# 00-Chopper-AB.net
KiCad netlist of a schematic drawn in Altium Designer
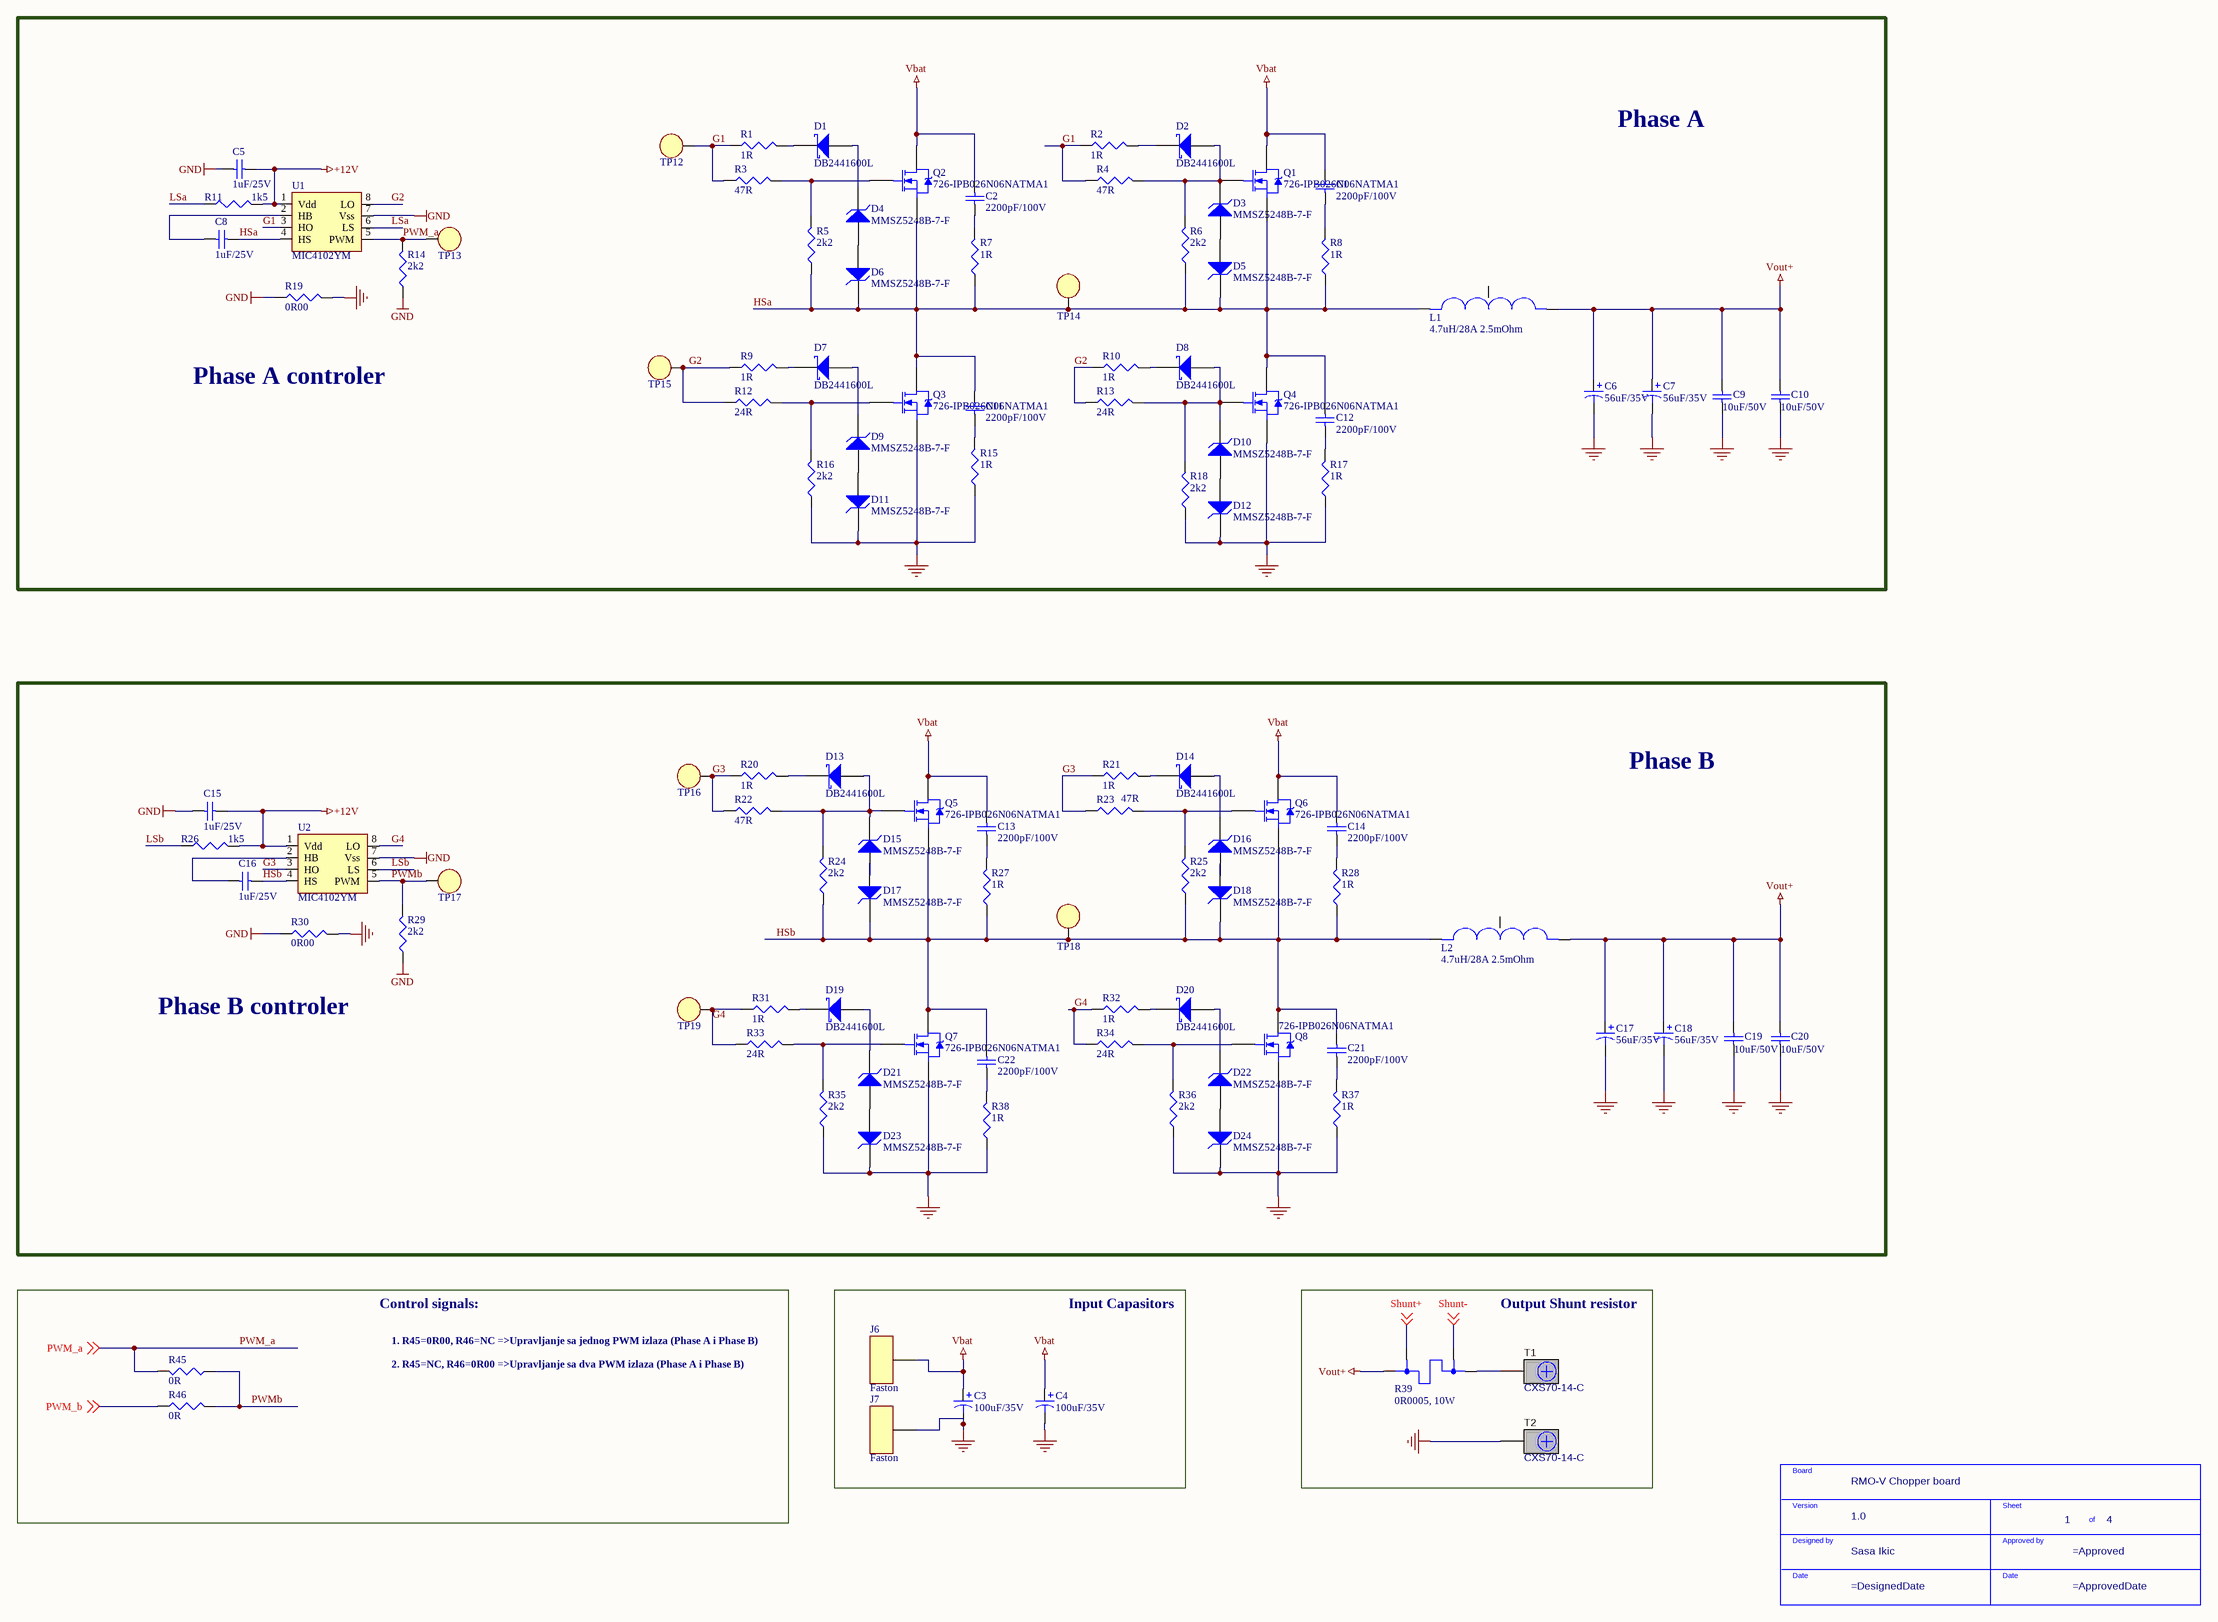
[diagram p0: 00-Chopper-AB.SchDoc]

(export (version "E")
  (design (tool "Eeschema 10.0.6"))
  (components
    (comp (ref "C1")
      (value "2200pF/100V")
      (footprint "DiscCapacitorSnuber")
      (description "D222K25Y5PH63J5R -  Ceramic Disc Capacitor, 2200 pF, 100 V, D Series, ± 10%, Y5P, 5 mm")
      (fields
        (field (name "MANUFACTURER") "Vishay")
        (field (name "MANUFACTURER PART NUMBER") "D222K25Y5PH63J5R")
      )
      (libsource (lib "RMOV_chopper") (part "D222K25Y5PH63J5R"))
    )
    (comp (ref "C2")
      (value "2200pF/100V")
      (footprint "DiscCapacitorSnuber")
      (description "D222K25Y5PH63J5R -  Ceramic Disc Capacitor, 2200 pF, 100 V, D Series, ± 10%, Y5P, 5 mm")
      (fields
        (field (name "MANUFACTURER") "Vishay")
        (field (name "MANUFACTURER PART NUMBER") "D222K25Y5PH63J5R")
      )
      (libsource (lib "RMOV_chopper") (part "D222K25Y5PH63J5R"))
    )
    (comp (ref "C3")
      (value "100uF/35V")
      (footprint "CAPAE8884X86M")
      (description "NICHICON         RHS1V101MCN1GS             ALUMINUM ELECTROLYTIC CAPACITOR, 100UF, 20%, 35V, SMD")
      (fields
        (field (name "MANUFACTURER") "Nichicon")
        (field (name "MANUFACTURER PART NUMBER") "RHS1V101MCN1GS")
      )
      (libsource (lib "RMOV_chopper") (part "RHS1V101MCN1GS"))
    )
    (comp (ref "C4")
      (value "100uF/35V")
      (footprint "CAPAE8884X86M")
      (description "NICHICON         RHS1V101MCN1GS             ALUMINUM ELECTROLYTIC CAPACITOR, 100UF, 20%, 35V, SMD")
      (fields
        (field (name "MANUFACTURER") "Nichicon")
        (field (name "MANUFACTURER PART NUMBER") "RHS1V101MCN1GS")
      )
      (libsource (lib "RMOV_chopper") (part "RHS1V101MCN1GS"))
    )
    (comp (ref "C5")
      (value "1uF/25V")
      (footprint "CAPC2013X14N")
      (description "1µF ±10% 25V Ceramic Capacitor X7R 0805 (2012 Metric)")
      (fields
        (field (name "MANUFACTURER") "Samsung Electro-Mechanics")
        (field (name "MANUFACTURER PART NUMBER") "CL21B105KAFNNNG")
      )
      (libsource (lib "RMOV_chopper") (part "CL21B105KAFNNNG"))
    )
    (comp (ref "C6")
      (value "56uF/35V")
      (footprint "CAPAE10184X100M")
      (description "56µF 35V Aluminum Polymer Capacitor Radial, Can - SMD 31mOhm 3000 Hrs @ 105°C")
      (fields
        (field (name "MANUFACTURER") "Nichicon")
        (field (name "MANUFACTURER PART NUMBER") "PCV1V560MCL1GS")
      )
      (libsource (lib "RMOV_chopper") (part "PCV1V560MCL1GS"))
    )
    (comp (ref "C7")
      (value "56uF/35V")
      (footprint "CAPAE10184X100M")
      (description "56µF 35V Aluminum Polymer Capacitor Radial, Can - SMD 31mOhm 3000 Hrs @ 105°C")
      (fields
        (field (name "MANUFACTURER") "Nichicon")
        (field (name "MANUFACTURER PART NUMBER") "PCV1V560MCL1GS")
      )
      (libsource (lib "RMOV_chopper") (part "PCV1V560MCL1GS"))
    )
    (comp (ref "C8")
      (value "1uF/25V")
      (footprint "CAPC2013X14N")
      (description "1µF ±10% 25V Ceramic Capacitor X7R 0805 (2012 Metric)")
      (fields
        (field (name "MANUFACTURER") "Samsung Electro-Mechanics")
        (field (name "MANUFACTURER PART NUMBER") "CL21B105KAFNNNG")
      )
      (libsource (lib "RMOV_chopper") (part "CL21B105KAFNNNG"))
    )
    (comp (ref "C9")
      (value "10uF/50V")
      (footprint "CAPC3426X27N")
      (description "10µF ±20% 50V Ceramic Capacitor X7S 1210 (3225 Metric)")
      (fields
        (field (name "MANUFACTURER") "Taiyo Yuden")
        (field (name "MANUFACTURER PART NUMBER") "UMK325C7106MM-T")
      )
      (libsource (lib "RMOV_chopper") (part "UMK325C7106MM-T"))
    )
    (comp (ref "C10")
      (value "10uF/50V")
      (footprint "CAPC3426X27N")
      (description "10µF ±20% 50V Ceramic Capacitor X7S 1210 (3225 Metric)")
      (fields
        (field (name "MANUFACTURER") "Taiyo Yuden")
        (field (name "MANUFACTURER PART NUMBER") "UMK325C7106MM-T")
      )
      (libsource (lib "RMOV_chopper") (part "UMK325C7106MM-T"))
    )
    (comp (ref "C11")
      (value "2200pF/100V")
      (footprint "DiscCapacitorSnuber")
      (description "D222K25Y5PH63J5R -  Ceramic Disc Capacitor, 2200 pF, 100 V, D Series, ± 10%, Y5P, 5 mm")
      (fields
        (field (name "MANUFACTURER") "Vishay")
        (field (name "MANUFACTURER PART NUMBER") "D222K25Y5PH63J5R")
      )
      (libsource (lib "RMOV_chopper") (part "D222K25Y5PH63J5R"))
    )
    (comp (ref "C12")
      (value "2200pF/100V")
      (footprint "DiscCapacitorSnuber")
      (description "D222K25Y5PH63J5R -  Ceramic Disc Capacitor, 2200 pF, 100 V, D Series, ± 10%, Y5P, 5 mm")
      (fields
        (field (name "MANUFACTURER") "Vishay")
        (field (name "MANUFACTURER PART NUMBER") "D222K25Y5PH63J5R")
      )
      (libsource (lib "RMOV_chopper") (part "D222K25Y5PH63J5R"))
    )
    (comp (ref "C13")
      (value "2200pF/100V")
      (footprint "DiscCapacitorSnuber")
      (description "D222K25Y5PH63J5R -  Ceramic Disc Capacitor, 2200 pF, 100 V, D Series, ± 10%, Y5P, 5 mm")
      (fields
        (field (name "MANUFACTURER") "Vishay")
        (field (name "MANUFACTURER PART NUMBER") "D222K25Y5PH63J5R")
      )
      (libsource (lib "RMOV_chopper") (part "D222K25Y5PH63J5R"))
    )
    (comp (ref "C14")
      (value "2200pF/100V")
      (footprint "DiscCapacitorSnuber")
      (description "D222K25Y5PH63J5R -  Ceramic Disc Capacitor, 2200 pF, 100 V, D Series, ± 10%, Y5P, 5 mm")
      (fields
        (field (name "MANUFACTURER") "Vishay")
        (field (name "MANUFACTURER PART NUMBER") "D222K25Y5PH63J5R")
      )
      (libsource (lib "RMOV_chopper") (part "D222K25Y5PH63J5R"))
    )
    (comp (ref "C15")
      (value "1uF/25V")
      (footprint "CAPC2013X14N")
      (description "1µF ±10% 25V Ceramic Capacitor X7R 0805 (2012 Metric)")
      (fields
        (field (name "MANUFACTURER") "Samsung Electro-Mechanics")
        (field (name "MANUFACTURER PART NUMBER") "CL21B105KAFNNNG")
      )
      (libsource (lib "RMOV_chopper") (part "CL21B105KAFNNNG"))
    )
    (comp (ref "C16")
      (value "1uF/25V")
      (footprint "CAPC2013X14N")
      (description "1µF ±10% 25V Ceramic Capacitor X7R 0805 (2012 Metric)")
      (fields
        (field (name "MANUFACTURER") "Samsung Electro-Mechanics")
        (field (name "MANUFACTURER PART NUMBER") "CL21B105KAFNNNG")
      )
      (libsource (lib "RMOV_chopper") (part "CL21B105KAFNNNG"))
    )
    (comp (ref "C17")
      (value "56uF/35V")
      (footprint "CAPAE10184X100M")
      (description "56µF 35V Aluminum Polymer Capacitor Radial, Can - SMD 31mOhm 3000 Hrs @ 105°C")
      (fields
        (field (name "MANUFACTURER") "Nichicon")
        (field (name "MANUFACTURER PART NUMBER") "PCV1V560MCL1GS")
      )
      (libsource (lib "RMOV_chopper") (part "PCV1V560MCL1GS"))
    )
    (comp (ref "C18")
      (value "56uF/35V")
      (footprint "CAPAE10184X100M")
      (description "56µF 35V Aluminum Polymer Capacitor Radial, Can - SMD 31mOhm 3000 Hrs @ 105°C")
      (fields
        (field (name "MANUFACTURER") "Nichicon")
        (field (name "MANUFACTURER PART NUMBER") "PCV1V560MCL1GS")
      )
      (libsource (lib "RMOV_chopper") (part "PCV1V560MCL1GS"))
    )
    (comp (ref "C19")
      (value "10uF/50V")
      (footprint "CAPC3426X27N")
      (description "10µF ±20% 50V Ceramic Capacitor X7S 1210 (3225 Metric)")
      (fields
        (field (name "MANUFACTURER") "Taiyo Yuden")
        (field (name "MANUFACTURER PART NUMBER") "UMK325C7106MM-T")
      )
      (libsource (lib "RMOV_chopper") (part "UMK325C7106MM-T"))
    )
    (comp (ref "C20")
      (value "10uF/50V")
      (footprint "CAPC3426X27N")
      (description "10µF ±20% 50V Ceramic Capacitor X7S 1210 (3225 Metric)")
      (fields
        (field (name "MANUFACTURER") "Taiyo Yuden")
        (field (name "MANUFACTURER PART NUMBER") "UMK325C7106MM-T")
      )
      (libsource (lib "RMOV_chopper") (part "UMK325C7106MM-T"))
    )
    (comp (ref "C21")
      (value "2200pF/100V")
      (footprint "DiscCapacitorSnuber")
      (description "D222K25Y5PH63J5R -  Ceramic Disc Capacitor, 2200 pF, 100 V, D Series, ± 10%, Y5P, 5 mm")
      (fields
        (field (name "MANUFACTURER") "Vishay")
        (field (name "MANUFACTURER PART NUMBER") "D222K25Y5PH63J5R")
      )
      (libsource (lib "RMOV_chopper") (part "D222K25Y5PH63J5R"))
    )
    (comp (ref "C22")
      (value "2200pF/100V")
      (footprint "DiscCapacitorSnuber")
      (description "D222K25Y5PH63J5R -  Ceramic Disc Capacitor, 2200 pF, 100 V, D Series, ± 10%, Y5P, 5 mm")
      (fields
        (field (name "MANUFACTURER") "Vishay")
        (field (name "MANUFACTURER PART NUMBER") "D222K25Y5PH63J5R")
      )
      (libsource (lib "RMOV_chopper") (part "D222K25Y5PH63J5R"))
    )
    (comp (ref "D1")
      (value "DB2441600L")
      (footprint "DIOM4824X10N")
      (description "Diodes - General Purpose, Power, Switching Schottky Barrier Diode")
      (fields (field (name "MANUFACTURER") "Panasonic"))
      (libsource (lib "RMOV_chopper") (part "DB2441600L"))
    )
    (comp (ref "D2")
      (value "DB2441600L")
      (footprint "DIOM4824X10N")
      (description "Diodes - General Purpose, Power, Switching Schottky Barrier Diode")
      (fields (field (name "MANUFACTURER") "Panasonic"))
      (libsource (lib "RMOV_chopper") (part "DB2441600L"))
    )
    (comp (ref "D3")
      (value "MMSZ5248B-7-F")
      (footprint "DIOM3715X14N")
      (description "Diodes Inc, 18V Zener Diode 5% 500 mW SMT 2-Pin SOD-123")
      (fields (field (name "MANUFACTURER") "Diode Zetex"))
      (libsource (lib "RMOV_chopper") (part "MMSZ5248B-7-F"))
    )
    (comp (ref "D4")
      (value "MMSZ5248B-7-F")
      (footprint "DIOM3715X14N")
      (description "Diodes Inc, 18V Zener Diode 5% 500 mW SMT 2-Pin SOD-123")
      (fields (field (name "MANUFACTURER") "Diode Zetex"))
      (libsource (lib "RMOV_chopper") (part "MMSZ5248B-7-F"))
    )
    (comp (ref "D5")
      (value "MMSZ5248B-7-F")
      (footprint "DIOM3715X14N")
      (description "Diodes Inc, 18V Zener Diode 5% 500 mW SMT 2-Pin SOD-123")
      (fields (field (name "MANUFACTURER") "Diode Zetex"))
      (libsource (lib "RMOV_chopper") (part "MMSZ5248B-7-F"))
    )
    (comp (ref "D6")
      (value "MMSZ5248B-7-F")
      (footprint "DIOM3715X14N")
      (description "Diodes Inc, 18V Zener Diode 5% 500 mW SMT 2-Pin SOD-123")
      (fields (field (name "MANUFACTURER") "Diode Zetex"))
      (libsource (lib "RMOV_chopper") (part "MMSZ5248B-7-F"))
    )
    (comp (ref "D7")
      (value "DB2441600L")
      (footprint "DIOM4824X10N")
      (description "Diodes - General Purpose, Power, Switching Schottky Barrier Diode")
      (fields (field (name "MANUFACTURER") "Panasonic"))
      (libsource (lib "RMOV_chopper") (part "DB2441600L"))
    )
    (comp (ref "D8")
      (value "DB2441600L")
      (footprint "DIOM4824X10N")
      (description "Diodes - General Purpose, Power, Switching Schottky Barrier Diode")
      (fields (field (name "MANUFACTURER") "Panasonic"))
      (libsource (lib "RMOV_chopper") (part "DB2441600L"))
    )
    (comp (ref "D9")
      (value "MMSZ5248B-7-F")
      (footprint "DIOM3715X14N")
      (description "Diodes Inc, 18V Zener Diode 5% 500 mW SMT 2-Pin SOD-123")
      (fields (field (name "MANUFACTURER") "Diode Zetex"))
      (libsource (lib "RMOV_chopper") (part "MMSZ5248B-7-F"))
    )
    (comp (ref "D10")
      (value "MMSZ5248B-7-F")
      (footprint "DIOM3715X14N")
      (description "Diodes Inc, 18V Zener Diode 5% 500 mW SMT 2-Pin SOD-123")
      (fields (field (name "MANUFACTURER") "Diode Zetex"))
      (libsource (lib "RMOV_chopper") (part "MMSZ5248B-7-F"))
    )
    (comp (ref "D11")
      (value "MMSZ5248B-7-F")
      (footprint "DIOM3715X14N")
      (description "Diodes Inc, 18V Zener Diode 5% 500 mW SMT 2-Pin SOD-123")
      (fields (field (name "MANUFACTURER") "Diode Zetex"))
      (libsource (lib "RMOV_chopper") (part "MMSZ5248B-7-F"))
    )
    (comp (ref "D12")
      (value "MMSZ5248B-7-F")
      (footprint "DIOM3715X14N")
      (description "Diodes Inc, 18V Zener Diode 5% 500 mW SMT 2-Pin SOD-123")
      (fields (field (name "MANUFACTURER") "Diode Zetex"))
      (libsource (lib "RMOV_chopper") (part "MMSZ5248B-7-F"))
    )
    (comp (ref "D13")
      (value "DB2441600L")
      (footprint "DIOM4824X10N")
      (description "Diodes - General Purpose, Power, Switching Schottky Barrier Diode")
      (fields (field (name "MANUFACTURER") "Panasonic"))
      (libsource (lib "RMOV_chopper") (part "DB2441600L"))
    )
    (comp (ref "D14")
      (value "DB2441600L")
      (footprint "DIOM4824X10N")
      (description "Diodes - General Purpose, Power, Switching Schottky Barrier Diode")
      (fields (field (name "MANUFACTURER") "Panasonic"))
      (libsource (lib "RMOV_chopper") (part "DB2441600L"))
    )
    (comp (ref "D15")
      (value "MMSZ5248B-7-F")
      (footprint "DIOM3715X14N")
      (description "Diodes Inc, 18V Zener Diode 5% 500 mW SMT 2-Pin SOD-123")
      (fields (field (name "MANUFACTURER") "Diode Zetex"))
      (libsource (lib "RMOV_chopper") (part "MMSZ5248B-7-F"))
    )
    (comp (ref "D16")
      (value "MMSZ5248B-7-F")
      (footprint "DIOM3715X14N")
      (description "Diodes Inc, 18V Zener Diode 5% 500 mW SMT 2-Pin SOD-123")
      (fields (field (name "MANUFACTURER") "Diode Zetex"))
      (libsource (lib "RMOV_chopper") (part "MMSZ5248B-7-F"))
    )
    (comp (ref "D17")
      (value "MMSZ5248B-7-F")
      (footprint "DIOM3715X14N")
      (description "Diodes Inc, 18V Zener Diode 5% 500 mW SMT 2-Pin SOD-123")
      (fields (field (name "MANUFACTURER") "Diode Zetex"))
      (libsource (lib "RMOV_chopper") (part "MMSZ5248B-7-F"))
    )
    (comp (ref "D18")
      (value "MMSZ5248B-7-F")
      (footprint "DIOM3715X14N")
      (description "Diodes Inc, 18V Zener Diode 5% 500 mW SMT 2-Pin SOD-123")
      (fields (field (name "MANUFACTURER") "Diode Zetex"))
      (libsource (lib "RMOV_chopper") (part "MMSZ5248B-7-F"))
    )
    (comp (ref "D19")
      (value "DB2441600L")
      (footprint "DIOM4824X10N")
      (description "Diodes - General Purpose, Power, Switching Schottky Barrier Diode")
      (fields (field (name "MANUFACTURER") "Panasonic"))
      (libsource (lib "RMOV_chopper") (part "DB2441600L"))
    )
    (comp (ref "D20")
      (value "DB2441600L")
      (footprint "DIOM4824X10N")
      (description "Diodes - General Purpose, Power, Switching Schottky Barrier Diode")
      (fields (field (name "MANUFACTURER") "Panasonic"))
      (libsource (lib "RMOV_chopper") (part "DB2441600L"))
    )
    (comp (ref "D21")
      (value "MMSZ5248B-7-F")
      (footprint "DIOM3715X14N")
      (description "Diodes Inc, 18V Zener Diode 5% 500 mW SMT 2-Pin SOD-123")
      (fields (field (name "MANUFACTURER") "Diode Zetex"))
      (libsource (lib "RMOV_chopper") (part "MMSZ5248B-7-F"))
    )
    (comp (ref "D22")
      (value "MMSZ5248B-7-F")
      (footprint "DIOM3715X14N")
      (description "Diodes Inc, 18V Zener Diode 5% 500 mW SMT 2-Pin SOD-123")
      (fields (field (name "MANUFACTURER") "Diode Zetex"))
      (libsource (lib "RMOV_chopper") (part "MMSZ5248B-7-F"))
    )
    (comp (ref "D23")
      (value "MMSZ5248B-7-F")
      (footprint "DIOM3715X14N")
      (description "Diodes Inc, 18V Zener Diode 5% 500 mW SMT 2-Pin SOD-123")
      (fields (field (name "MANUFACTURER") "Diode Zetex"))
      (libsource (lib "RMOV_chopper") (part "MMSZ5248B-7-F"))
    )
    (comp (ref "D24")
      (value "MMSZ5248B-7-F")
      (footprint "DIOM3715X14N")
      (description "Diodes Inc, 18V Zener Diode 5% 500 mW SMT 2-Pin SOD-123")
      (fields (field (name "MANUFACTURER") "Diode Zetex"))
      (libsource (lib "RMOV_chopper") (part "MMSZ5248B-7-F"))
    )
    (comp (ref "J6")
      (value "Faston")
      (footprint "KONEKTOR-I-FASTON")
      (description "KONEKTOR FASTON OBICNI")
      (libsource (lib "My Library") (part "Faston Konektor"))
    )
    (comp (ref "J7")
      (value "Faston")
      (footprint "KONEKTOR-I-FASTON")
      (description "KONEKTOR FASTON OBICNI")
      (libsource (lib "My Library") (part "Faston Konektor"))
    )
    (comp (ref "L1")
      (value "4.7uH/28A 2.5mOhm")
      (footprint "BournsInductor_4.7uH")
      (description "FIXED IND 4.7UH 28A 2.5MOHM SMD")
      (fields
        (field (name "MANUFACTURER") "Bourns")
        (field (name "MANUFACTURER PART NUMBER") "PQ2617BHA-4R7K")
      )
      (libsource (lib "RMOV_chopper") (part "PQ2617BHA-4R7K"))
    )
    (comp (ref "L2")
      (value "4.7uH/28A 2.5mOhm")
      (footprint "BournsInductor_4.7uH")
      (description "FIXED IND 4.7UH 28A 2.5MOHM SMD")
      (fields
        (field (name "MANUFACTURER") "Bourns")
        (field (name "MANUFACTURER PART NUMBER") "PQ2617BHA-4R7K")
      )
      (libsource (lib "RMOV_chopper") (part "PQ2617BHA-4R7K"))
    )
    (comp (ref "Q1")
      (value "726-IPB026N06NATMA1")
      (footprint "DPAK508P1524X457-3N - duplicate")
      (description "MOSFET N-Ch 60V 100A D2PAK-2")
      (fields
        (field (name "MANUFACTURER") "Infineon Technologies")
        (field (name "MANUFACTURER PART NUMBER") "IPB026N06NATMA1")
      )
      (libsource (lib "RMOV_chopper") (part "IPB026N06NATMA1"))
    )
    (comp (ref "Q2")
      (value "726-IPB026N06NATMA1")
      (footprint "DPAK508P1524X457-3N - duplicate")
      (description "MOSFET N-Ch 60V 100A D2PAK-2")
      (fields
        (field (name "MANUFACTURER") "Infineon Technologies")
        (field (name "MANUFACTURER PART NUMBER") "IPB026N06NATMA1")
      )
      (libsource (lib "RMOV_chopper") (part "IPB026N06NATMA1"))
    )
    (comp (ref "Q3")
      (value "726-IPB026N06NATMA1")
      (footprint "DPAK508P1524X457-3N - duplicate")
      (description "MOSFET N-Ch 60V 100A D2PAK-2")
      (fields
        (field (name "MANUFACTURER") "Infineon Technologies")
        (field (name "MANUFACTURER PART NUMBER") "IPB026N06NATMA1")
      )
      (libsource (lib "RMOV_chopper") (part "IPB026N06NATMA1"))
    )
    (comp (ref "Q4")
      (value "726-IPB026N06NATMA1")
      (footprint "DPAK508P1524X457-3N - duplicate")
      (description "MOSFET N-Ch 60V 100A D2PAK-2")
      (fields
        (field (name "MANUFACTURER") "Infineon Technologies")
        (field (name "MANUFACTURER PART NUMBER") "IPB026N06NATMA1")
      )
      (libsource (lib "RMOV_chopper") (part "IPB026N06NATMA1"))
    )
    (comp (ref "Q5")
      (value "726-IPB026N06NATMA1")
      (footprint "DPAK508P1524X457-3N - duplicate")
      (description "MOSFET N-Ch 60V 100A D2PAK-2")
      (fields
        (field (name "MANUFACTURER") "Infineon Technologies")
        (field (name "MANUFACTURER PART NUMBER") "IPB026N06NATMA1")
      )
      (libsource (lib "RMOV_chopper") (part "IPB026N06NATMA1"))
    )
    (comp (ref "Q6")
      (value "726-IPB026N06NATMA1")
      (footprint "DPAK508P1524X457-3N - duplicate")
      (description "MOSFET N-Ch 60V 100A D2PAK-2")
      (fields
        (field (name "MANUFACTURER") "Infineon Technologies")
        (field (name "MANUFACTURER PART NUMBER") "IPB026N06NATMA1")
      )
      (libsource (lib "RMOV_chopper") (part "IPB026N06NATMA1"))
    )
    (comp (ref "Q7")
      (value "726-IPB026N06NATMA1")
      (footprint "DPAK508P1524X457-3N - duplicate")
      (description "MOSFET N-Ch 60V 100A D2PAK-2")
      (fields
        (field (name "MANUFACTURER") "Infineon Technologies")
        (field (name "MANUFACTURER PART NUMBER") "IPB026N06NATMA1")
      )
      (libsource (lib "RMOV_chopper") (part "IPB026N06NATMA1"))
    )
    (comp (ref "Q8")
      (value "726-IPB026N06NATMA1")
      (footprint "DPAK508P1524X457-3N - duplicate")
      (description "MOSFET N-Ch 60V 100A D2PAK-2")
      (fields
        (field (name "MANUFACTURER") "Infineon Technologies")
        (field (name "MANUFACTURER PART NUMBER") "IPB026N06NATMA1")
      )
      (libsource (lib "RMOV_chopper") (part "IPB026N06NATMA1"))
    )
    (comp (ref "R1")
      (value "1R")
      (footprint "RESC2914X05N")
      (description "Res Thick Film 0805 1 Ohm 1% 1/8W ±100ppm/°C Molded SMD SMD Paper T/R")
      (fields
        (field (name "MANUFACTURER") "Vishay")
        (field (name "MANUFACTURER PART NUMBER") "CRCW08051R00FKEA")
      )
      (libsource (lib "RMOV_chopper") (part "CRCW08051R00FKEA"))
    )
    (comp (ref "R2")
      (value "1R")
      (footprint "RESC2914X05N")
      (description "Res Thick Film 0805 1 Ohm 1% 1/8W ±100ppm/°C Molded SMD SMD Paper T/R")
      (fields
        (field (name "MANUFACTURER") "Vishay")
        (field (name "MANUFACTURER PART NUMBER") "CRCW08051R00FKEA")
      )
      (libsource (lib "RMOV_chopper") (part "CRCW08051R00FKEA"))
    )
    (comp (ref "R3")
      (value "47R")
      (footprint "RESC2914X05N")
      (description "RC Series 0805 0.125 W 47 Ohm ±1% ±100 ppm/°C SMT Thick Film Chip Resistor")
      (fields
        (field (name "MANUFACTURER") "Yageo")
        (field (name "MANUFACTURER PART NUMBER") "RC0805FR-0747RL")
      )
      (libsource (lib "RMOV_chopper") (part "RC0805FR-0747RL"))
    )
    (comp (ref "R4")
      (value "47R")
      (footprint "RESC2914X05N")
      (description "RC Series 0805 0.125 W 47 Ohm ±1% ±100 ppm/°C SMT Thick Film Chip Resistor")
      (fields
        (field (name "MANUFACTURER") "Yageo")
        (field (name "MANUFACTURER PART NUMBER") "RC0805FR-0747RL")
      )
      (libsource (lib "RMOV_chopper") (part "RC0805FR-0747RL"))
    )
    (comp (ref "R5")
      (value "2k2")
      (footprint "RESC2914X05N")
      (description "RC Series 0805 0.125 W 2.2 kOhm ±1% ±100 ppm/°C SMT Thick Film Chip Resistor")
      (fields
        (field (name "MANUFACTURER") "Yageo")
        (field (name "MANUFACTURER PART NUMBER") "RC0805FR-072K2L")
      )
      (libsource (lib "RMOV_chopper") (part "RC0805FR-072K2L"))
    )
    (comp (ref "R6")
      (value "2k2")
      (footprint "RESC2914X05N")
      (description "RC Series 0805 0.125 W 2.2 kOhm ±1% ±100 ppm/°C SMT Thick Film Chip Resistor")
      (fields
        (field (name "MANUFACTURER") "Yageo")
        (field (name "MANUFACTURER PART NUMBER") "RC0805FR-072K2L")
      )
      (libsource (lib "RMOV_chopper") (part "RC0805FR-072K2L"))
    )
    (comp (ref "R7")
      (value "1R")
      (footprint "RESC6432X08N")
      (description "Thick Film Resistors - SMD CHIP RESISTOR")
      (fields
        (field (name "MANUFACTURER") "Bourns")
        (field (name "MANUFACTURER PART NUMBER") "CR2512-J/-1R0ELF")
      )
      (libsource (lib "RMOV_chopper") (part "CR2512-J/-1R0ELF"))
    )
    (comp (ref "R8")
      (value "1R")
      (footprint "RESC6432X08N")
      (description "Thick Film Resistors - SMD CHIP RESISTOR")
      (fields
        (field (name "MANUFACTURER") "Bourns")
        (field (name "MANUFACTURER PART NUMBER") "CR2512-J/-1R0ELF")
      )
      (libsource (lib "RMOV_chopper") (part "CR2512-J/-1R0ELF"))
    )
    (comp (ref "R9")
      (value "1R")
      (footprint "RESC2914X05N")
      (description "Res Thick Film 0805 1 Ohm 1% 1/8W ±100ppm/°C Molded SMD SMD Paper T/R")
      (fields
        (field (name "MANUFACTURER") "Vishay")
        (field (name "MANUFACTURER PART NUMBER") "CRCW08051R00FKEA")
      )
      (libsource (lib "RMOV_chopper") (part "CRCW08051R00FKEA"))
    )
    (comp (ref "R10")
      (value "1R")
      (footprint "RESC2914X05N")
      (description "Res Thick Film 0805 1 Ohm 1% 1/8W ±100ppm/°C Molded SMD SMD Paper T/R")
      (fields
        (field (name "MANUFACTURER") "Vishay")
        (field (name "MANUFACTURER PART NUMBER") "CRCW08051R00FKEA")
      )
      (libsource (lib "RMOV_chopper") (part "CRCW08051R00FKEA"))
    )
    (comp (ref "R11")
      (value "1k5")
      (footprint "RESC2914X05N")
      (description "Res Thick Film 0805 1.5K Ohm 1% 1/8W ±100ppm/°C Molded SMD Paper T/R")
      (fields
        (field (name "MANUFACTURER") "Vishay")
        (field (name "MANUFACTURER PART NUMBER") "CRCW08051K50FKEA")
      )
      (libsource (lib "RMOV_chopper") (part "CRCW08051K50FKEA"))
    )
    (comp (ref "R12")
      (value "24R")
      (footprint "RESC2914X05N")
      (description "Res Thick Film 0805 24 Ohm 1% 1/8W ±100ppm/°C Molded SMD Paper T/R")
      (fields
        (field (name "MANUFACTURER") "Vishay")
        (field (name "MANUFACTURER PART NUMBER") "CRCW080524R0FKEA")
      )
      (libsource (lib "RMOV_chopper") (part "CRCW080524R0FKEA"))
    )
    (comp (ref "R13")
      (value "24R")
      (footprint "RESC2914X05N")
      (description "Res Thick Film 0805 24 Ohm 1% 1/8W ±100ppm/°C Molded SMD Paper T/R")
      (fields
        (field (name "MANUFACTURER") "Vishay")
        (field (name "MANUFACTURER PART NUMBER") "CRCW080524R0FKEA")
      )
      (libsource (lib "RMOV_chopper") (part "CRCW080524R0FKEA"))
    )
    (comp (ref "R14")
      (value "2k2")
      (footprint "RESC2914X05N")
      (description "RC Series 0805 0.125 W 2.2 kOhm ±1% ±100 ppm/°C SMT Thick Film Chip Resistor")
      (fields
        (field (name "MANUFACTURER") "Yageo")
        (field (name "MANUFACTURER PART NUMBER") "RC0805FR-072K2L")
      )
      (libsource (lib "RMOV_chopper") (part "RC0805FR-072K2L"))
    )
    (comp (ref "R15")
      (value "1R")
      (footprint "RESC6432X08N")
      (description "Thick Film Resistors - SMD CHIP RESISTOR")
      (fields
        (field (name "MANUFACTURER") "Bourns")
        (field (name "MANUFACTURER PART NUMBER") "CR2512-J/-1R0ELF")
      )
      (libsource (lib "RMOV_chopper") (part "CR2512-J/-1R0ELF"))
    )
    (comp (ref "R16")
      (value "2k2")
      (footprint "RESC2914X05N")
      (description "RC Series 0805 0.125 W 2.2 kOhm ±1% ±100 ppm/°C SMT Thick Film Chip Resistor")
      (fields
        (field (name "MANUFACTURER") "Yageo")
        (field (name "MANUFACTURER PART NUMBER") "RC0805FR-072K2L")
      )
      (libsource (lib "RMOV_chopper") (part "RC0805FR-072K2L"))
    )
    (comp (ref "R17")
      (value "1R")
      (footprint "RESC6432X08N")
      (description "Thick Film Resistors - SMD CHIP RESISTOR")
      (fields
        (field (name "MANUFACTURER") "Bourns")
        (field (name "MANUFACTURER PART NUMBER") "CR2512-J/-1R0ELF")
      )
      (libsource (lib "RMOV_chopper") (part "CR2512-J/-1R0ELF"))
    )
    (comp (ref "R18")
      (value "2k2")
      (footprint "RESC2914X05N")
      (description "RC Series 0805 0.125 W 2.2 kOhm ±1% ±100 ppm/°C SMT Thick Film Chip Resistor")
      (fields
        (field (name "MANUFACTURER") "Yageo")
        (field (name "MANUFACTURER PART NUMBER") "RC0805FR-072K2L")
      )
      (libsource (lib "RMOV_chopper") (part "RC0805FR-072K2L"))
    )
    (comp (ref "R19")
      (value "0R00")
      (footprint "RESC2914X05N")
      (description "Res Thick Film 0805 0 Ohm Jumper Molded SMD Paper T/R")
      (fields
        (field (name "MANUFACTURER") "Yageo")
        (field (name "MANUFACTURER PART NUMBER") "RC0805FR-070RL")
      )
      (libsource (lib "RMOV_chopper") (part "RC0805FR-070RL"))
    )
    (comp (ref "R20")
      (value "1R")
      (footprint "RESC2914X05N")
      (description "Res Thick Film 0805 1 Ohm 1% 1/8W ±100ppm/°C Molded SMD SMD Paper T/R")
      (fields
        (field (name "MANUFACTURER") "Vishay")
        (field (name "MANUFACTURER PART NUMBER") "CRCW08051R00FKEA")
      )
      (libsource (lib "RMOV_chopper") (part "CRCW08051R00FKEA"))
    )
    (comp (ref "R21")
      (value "1R")
      (footprint "RESC2914X05N")
      (description "Res Thick Film 0805 1 Ohm 1% 1/8W ±100ppm/°C Molded SMD SMD Paper T/R")
      (fields
        (field (name "MANUFACTURER") "Vishay")
        (field (name "MANUFACTURER PART NUMBER") "CRCW08051R00FKEA")
      )
      (libsource (lib "RMOV_chopper") (part "CRCW08051R00FKEA"))
    )
    (comp (ref "R22")
      (value "47R")
      (footprint "RESC2914X05N")
      (description "RC Series 0805 0.125 W 47 Ohm ±1% ±100 ppm/°C SMT Thick Film Chip Resistor")
      (fields
        (field (name "MANUFACTURER") "Yageo")
        (field (name "MANUFACTURER PART NUMBER") "RC0805FR-0747RL")
      )
      (libsource (lib "RMOV_chopper") (part "RC0805FR-0747RL"))
    )
    (comp (ref "R23")
      (value "47R")
      (footprint "RESC2914X05N")
      (description "RC Series 0805 0.125 W 47 Ohm ±1% ±100 ppm/°C SMT Thick Film Chip Resistor")
      (fields
        (field (name "MANUFACTURER") "Yageo")
        (field (name "MANUFACTURER PART NUMBER") "RC0805FR-0747RL")
      )
      (libsource (lib "RMOV_chopper") (part "RC0805FR-0747RL"))
    )
    (comp (ref "R24")
      (value "2k2")
      (footprint "RESC2914X05N")
      (description "RC Series 0805 0.125 W 2.2 kOhm ±1% ±100 ppm/°C SMT Thick Film Chip Resistor")
      (fields
        (field (name "MANUFACTURER") "Yageo")
        (field (name "MANUFACTURER PART NUMBER") "RC0805FR-072K2L")
      )
      (libsource (lib "RMOV_chopper") (part "RC0805FR-072K2L"))
    )
    (comp (ref "R25")
      (value "2k2")
      (footprint "RESC2914X05N")
      (description "RC Series 0805 0.125 W 2.2 kOhm ±1% ±100 ppm/°C SMT Thick Film Chip Resistor")
      (fields
        (field (name "MANUFACTURER") "Yageo")
        (field (name "MANUFACTURER PART NUMBER") "RC0805FR-072K2L")
      )
      (libsource (lib "RMOV_chopper") (part "RC0805FR-072K2L"))
    )
    (comp (ref "R26")
      (value "1k5")
      (footprint "RESC2914X05N")
      (description "Res Thick Film 0805 1.5K Ohm 1% 1/8W ±100ppm/°C Molded SMD Paper T/R")
      (fields
        (field (name "MANUFACTURER") "Vishay")
        (field (name "MANUFACTURER PART NUMBER") "CRCW08051K50FKEA")
      )
      (libsource (lib "RMOV_chopper") (part "CRCW08051K50FKEA"))
    )
    (comp (ref "R27")
      (value "1R")
      (footprint "RESC6432X08N")
      (description "Thick Film Resistors - SMD CHIP RESISTOR")
      (fields
        (field (name "MANUFACTURER") "Bourns")
        (field (name "MANUFACTURER PART NUMBER") "CR2512-J/-1R0ELF")
      )
      (libsource (lib "RMOV_chopper") (part "CR2512-J/-1R0ELF"))
    )
    (comp (ref "R28")
      (value "1R")
      (footprint "RESC6432X08N")
      (description "Thick Film Resistors - SMD CHIP RESISTOR")
      (fields
        (field (name "MANUFACTURER") "Bourns")
        (field (name "MANUFACTURER PART NUMBER") "CR2512-J/-1R0ELF")
      )
      (libsource (lib "RMOV_chopper") (part "CR2512-J/-1R0ELF"))
    )
    (comp (ref "R29")
      (value "2k2")
      (footprint "RESC2914X05N")
      (description "RC Series 0805 0.125 W 2.2 kOhm ±1% ±100 ppm/°C SMT Thick Film Chip Resistor")
      (fields
        (field (name "MANUFACTURER") "Yageo")
        (field (name "MANUFACTURER PART NUMBER") "RC0805FR-072K2L")
      )
      (libsource (lib "RMOV_chopper") (part "RC0805FR-072K2L"))
    )
    (comp (ref "R30")
      (value "0R00")
      (footprint "RESC2914X05N")
      (description "Res Thick Film 0805 0 Ohm Jumper Molded SMD Paper T/R")
      (fields
        (field (name "MANUFACTURER") "Yageo")
        (field (name "MANUFACTURER PART NUMBER") "RC0805FR-070RL")
      )
      (libsource (lib "RMOV_chopper") (part "RC0805FR-070RL"))
    )
    (comp (ref "R31")
      (value "1R")
      (footprint "RESC2914X05N")
      (description "Res Thick Film 0805 1 Ohm 1% 1/8W ±100ppm/°C Molded SMD SMD Paper T/R")
      (fields
        (field (name "MANUFACTURER") "Vishay")
        (field (name "MANUFACTURER PART NUMBER") "CRCW08051R00FKEA")
      )
      (libsource (lib "RMOV_chopper") (part "CRCW08051R00FKEA"))
    )
    (comp (ref "R32")
      (value "1R")
      (footprint "RESC2914X05N")
      (description "Res Thick Film 0805 1 Ohm 1% 1/8W ±100ppm/°C Molded SMD SMD Paper T/R")
      (fields
        (field (name "MANUFACTURER") "Vishay")
        (field (name "MANUFACTURER PART NUMBER") "CRCW08051R00FKEA")
      )
      (libsource (lib "RMOV_chopper") (part "CRCW08051R00FKEA"))
    )
    (comp (ref "R33")
      (value "24R")
      (footprint "RESC2914X05N")
      (description "Res Thick Film 0805 24 Ohm 1% 1/8W ±100ppm/°C Molded SMD Paper T/R")
      (fields
        (field (name "MANUFACTURER") "Vishay")
        (field (name "MANUFACTURER PART NUMBER") "CRCW080524R0FKEA")
      )
      (libsource (lib "RMOV_chopper") (part "CRCW080524R0FKEA"))
    )
    (comp (ref "R34")
      (value "24R")
      (footprint "RESC2914X05N")
      (description "Res Thick Film 0805 24 Ohm 1% 1/8W ±100ppm/°C Molded SMD Paper T/R")
      (fields
        (field (name "MANUFACTURER") "Vishay")
        (field (name "MANUFACTURER PART NUMBER") "CRCW080524R0FKEA")
      )
      (libsource (lib "RMOV_chopper") (part "CRCW080524R0FKEA"))
    )
    (comp (ref "R35")
      (value "2k2")
      (footprint "RESC2914X05N")
      (description "RC Series 0805 0.125 W 2.2 kOhm ±1% ±100 ppm/°C SMT Thick Film Chip Resistor")
      (fields
        (field (name "MANUFACTURER") "Yageo")
        (field (name "MANUFACTURER PART NUMBER") "RC0805FR-072K2L")
      )
      (libsource (lib "RMOV_chopper") (part "RC0805FR-072K2L"))
    )
    (comp (ref "R36")
      (value "2k2")
      (footprint "RESC2914X05N")
      (description "RC Series 0805 0.125 W 2.2 kOhm ±1% ±100 ppm/°C SMT Thick Film Chip Resistor")
      (fields
        (field (name "MANUFACTURER") "Yageo")
        (field (name "MANUFACTURER PART NUMBER") "RC0805FR-072K2L")
      )
      (libsource (lib "RMOV_chopper") (part "RC0805FR-072K2L"))
    )
    (comp (ref "R37")
      (value "1R")
      (footprint "RESC6432X08N")
      (description "Thick Film Resistors - SMD CHIP RESISTOR")
      (fields
        (field (name "MANUFACTURER") "Bourns")
        (field (name "MANUFACTURER PART NUMBER") "CR2512-J/-1R0ELF")
      )
      (libsource (lib "RMOV_chopper") (part "CR2512-J/-1R0ELF"))
    )
    (comp (ref "R38")
      (value "1R")
      (footprint "RESC6432X08N")
      (description "Thick Film Resistors - SMD CHIP RESISTOR")
      (fields
        (field (name "MANUFACTURER") "Bourns")
        (field (name "MANUFACTURER PART NUMBER") "CR2512-J/-1R0ELF")
      )
      (libsource (lib "RMOV_chopper") (part "CR2512-J/-1R0ELF"))
    )
    (comp (ref "R39")
      (value "0R0005, 10W")
      (footprint "PBV")
      (description "SHENT 0R0005 10W THT")
      (libsource (lib "My Library") (part "Shent_THT"))
    )
    (comp (ref "R45")
      (value "0R")
      (footprint "R0805")
      (description "RES 0R00 0805 0.125W")
      (fields
        (field (name "MANUFACTURER") "Vishay Dale")
        (field (name "MANUFACTURER PART NUMBER") "CRCW08050000Z0EA")
        (field (name ".PCBCHECKED") "BP")
        (field (name ".SCHCHECKED") "BP")
      )
      (libsource (lib "My Library") (part "CRCW08050000Z0EA"))
    )
    (comp (ref "R46")
      (value "0R")
      (footprint "R0805")
      (description "RES 0R00 0805 0.125W")
      (fields
        (field (name "MANUFACTURER") "Vishay Dale")
        (field (name "MANUFACTURER PART NUMBER") "CRCW08050000Z0EA")
        (field (name ".PCBCHECKED") "BP")
        (field (name ".SCHCHECKED") "BP")
      )
      (libsource (lib "My Library") (part "CRCW08050000Z0EA"))
    )
    (comp (ref "T1")
      (value "CXS70-14-C")
      (footprint "Panduit_CXS70-14-C")
      (description "Terminal 70A Lug")
      (fields
        (field (name "MANUFACTURER") "Panduit")
        (field (name "SYMBOLCREATOR") "crossc")
        (field (name "PUBLISHER") "Texas Instruments")
      )
      (libsource (lib "My Library") (part "CXS70-14-C"))
    )
    (comp (ref "T2")
      (value "CXS70-14-C")
      (footprint "Panduit_CXS70-14-C")
      (description "Terminal 70A Lug")
      (fields
        (field (name "MANUFACTURER") "Panduit")
        (field (name "SYMBOLCREATOR") "crossc")
        (field (name "PUBLISHER") "Texas Instruments")
      )
      (libsource (lib "My Library") (part "CXS70-14-C"))
    )
    (comp (ref "TP12")
      (value "-")
      (footprint "TESTPOINT_0.8X1.5")
      (description "Testpoint 0.8mm X 1.5mm")
      (fields (field (name ".PCBCHECKED") "BP") (field (name ".SCHCHECKED") "BP"))
      (libsource (lib "My Library") (part "Testpoint"))
    )
    (comp (ref "TP13")
      (value "-")
      (footprint "TESTPOINT_0.8X1.5")
      (description "Testpoint 0.8mm X 1.5mm")
      (fields (field (name ".PCBCHECKED") "BP") (field (name ".SCHCHECKED") "BP"))
      (libsource (lib "My Library") (part "Testpoint"))
    )
    (comp (ref "TP14")
      (value "-")
      (footprint "TESTPOINT_0.8X1.5")
      (description "Testpoint 0.8mm X 1.5mm")
      (fields (field (name ".PCBCHECKED") "BP") (field (name ".SCHCHECKED") "BP"))
      (libsource (lib "My Library") (part "Testpoint"))
    )
    (comp (ref "TP15")
      (value "-")
      (footprint "TESTPOINT_0.8X1.5")
      (description "Testpoint 0.8mm X 1.5mm")
      (fields (field (name ".PCBCHECKED") "BP") (field (name ".SCHCHECKED") "BP"))
      (libsource (lib "My Library") (part "Testpoint"))
    )
    (comp (ref "TP16")
      (value "-")
      (footprint "TESTPOINT_0.8X1.5")
      (description "Testpoint 0.8mm X 1.5mm")
      (fields (field (name ".PCBCHECKED") "BP") (field (name ".SCHCHECKED") "BP"))
      (libsource (lib "My Library") (part "Testpoint"))
    )
    (comp (ref "TP17")
      (value "-")
      (footprint "TESTPOINT_0.8X1.5")
      (description "Testpoint 0.8mm X 1.5mm")
      (fields (field (name ".PCBCHECKED") "BP") (field (name ".SCHCHECKED") "BP"))
      (libsource (lib "My Library") (part "Testpoint"))
    )
    (comp (ref "TP18")
      (value "-")
      (footprint "TESTPOINT_0.8X1.5")
      (description "Testpoint 0.8mm X 1.5mm")
      (fields (field (name ".PCBCHECKED") "BP") (field (name ".SCHCHECKED") "BP"))
      (libsource (lib "My Library") (part "Testpoint"))
    )
    (comp (ref "TP19")
      (value "-")
      (footprint "TESTPOINT_0.8X1.5")
      (description "Testpoint 0.8mm X 1.5mm")
      (fields (field (name ".PCBCHECKED") "BP") (field (name ".SCHCHECKED") "BP"))
      (libsource (lib "My Library") (part "Testpoint"))
    )
    (comp (ref "U1")
      (value "MIC4102YM")
      (footprint "SOIC127P610X173-8N")
      (description "Gate Drivers 100V HalfBridge MOSFET Driver with Anti-Shoot-through Circuitry")
      (fields (field (name "MANUFACTURER") "Microchip"))
      (libsource (lib "RMOV_chopper") (part "MIC4102YM"))
    )
    (comp (ref "U2")
      (value "MIC4102YM")
      (footprint "SOIC127P610X173-8N")
      (description "Gate Drivers 100V HalfBridge MOSFET Driver with Anti-Shoot-through Circuitry")
      (fields (field (name "MANUFACTURER") "Microchip"))
      (libsource (lib "RMOV_chopper") (part "MIC4102YM"))
    )
  )
  (nets
    (net (code "1") (name "+12V") (class "Default")
      (node (ref "C15") (pin "2") (pinfunction "2_2") (pintype "passive"))
      (node (ref "C5") (pin "1") (pinfunction "1_1") (pintype "passive"))
      (node (ref "R11") (pin "2") (pinfunction "2_2") (pintype "passive"))
      (node (ref "R26") (pin "2") (pinfunction "2_2") (pintype "passive"))
      (node (ref "U1") (pin "1") (pinfunction "Vdd_1") (pintype "passive"))
      (node (ref "U2") (pin "1") (pinfunction "Vdd_1") (pintype "passive"))
    )
    (net (code "2") (name "/G1") (class "Default")
      (node (ref "R1") (pin "1") (pinfunction "1_1") (pintype "passive"))
      (node (ref "R2") (pin "1") (pinfunction "1_1") (pintype "passive"))
      (node (ref "R3") (pin "1") (pinfunction "1_1") (pintype "passive"))
      (node (ref "R4") (pin "1") (pinfunction "1_1") (pintype "passive"))
      (node (ref "TP12") (pin "1") (pinfunction "1_1") (pintype "passive"))
      (node (ref "U1") (pin "3") (pinfunction "HO_3") (pintype "passive"))
    )
    (net (code "3") (name "/G2") (class "Default")
      (node (ref "R10") (pin "1") (pinfunction "1_1") (pintype "passive"))
      (node (ref "R12") (pin "1") (pinfunction "1_1") (pintype "passive"))
      (node (ref "R13") (pin "1") (pinfunction "1_1") (pintype "passive"))
      (node (ref "R9") (pin "1") (pinfunction "1_1") (pintype "passive"))
      (node (ref "TP15") (pin "1") (pinfunction "1_1") (pintype "passive"))
      (node (ref "U1") (pin "8") (pinfunction "LO_8") (pintype "passive"))
    )
    (net (code "4") (name "/G3") (class "Default")
      (node (ref "R20") (pin "1") (pinfunction "1_1") (pintype "passive"))
      (node (ref "R21") (pin "1") (pinfunction "1_1") (pintype "passive"))
      (node (ref "R22") (pin "1") (pinfunction "1_1") (pintype "passive"))
      (node (ref "R23") (pin "1") (pinfunction "1_1") (pintype "passive"))
      (node (ref "TP16") (pin "1") (pinfunction "1_1") (pintype "passive"))
      (node (ref "U2") (pin "3") (pinfunction "HO_3") (pintype "passive"))
    )
    (net (code "5") (name "/G4") (class "Default")
      (node (ref "R31") (pin "1") (pinfunction "1_1") (pintype "passive"))
      (node (ref "R32") (pin "1") (pinfunction "1_1") (pintype "passive"))
      (node (ref "R33") (pin "1") (pinfunction "1_1") (pintype "passive"))
      (node (ref "R34") (pin "1") (pinfunction "1_1") (pintype "passive"))
      (node (ref "TP19") (pin "1") (pinfunction "1_1") (pintype "passive"))
      (node (ref "U2") (pin "8") (pinfunction "LO_8") (pintype "passive"))
    )
    (net (code "6") (name "/HSa") (class "Default")
      (node (ref "C11") (pin "2") (pinfunction "2_2") (pintype "passive"))
      (node (ref "C12") (pin "2") (pinfunction "2_2") (pintype "passive"))
      (node (ref "C8") (pin "1") (pinfunction "1_1") (pintype "passive"))
      (node (ref "D5") (pin "2") (pinfunction "K_2") (pintype "passive"))
      (node (ref "D6") (pin "2") (pinfunction "K_2") (pintype "passive"))
      (node (ref "L1") (pin "1") (pinfunction "1_1") (pintype "passive"))
      (node (ref "Q1") (pin "3") (pinfunction "3_3") (pintype "passive"))
      (node (ref "Q2") (pin "3") (pinfunction "3_3") (pintype "passive"))
      (node (ref "Q3") (pin "2") (pinfunction "2_2") (pintype "passive"))
      (node (ref "Q4") (pin "2") (pinfunction "2_2") (pintype "passive"))
      (node (ref "R5") (pin "1") (pinfunction "1_1") (pintype "passive"))
      (node (ref "R6") (pin "1") (pinfunction "1_1") (pintype "passive"))
      (node (ref "R7") (pin "1") (pinfunction "1_1") (pintype "passive"))
      (node (ref "R8") (pin "1") (pinfunction "1_1") (pintype "passive"))
      (node (ref "TP14") (pin "1") (pinfunction "1_1") (pintype "passive"))
      (node (ref "U1") (pin "4") (pinfunction "HS_4") (pintype "passive"))
    )
    (net (code "7") (name "/HSb") (class "Default")
      (node (ref "C16") (pin "1") (pinfunction "1_1") (pintype "passive"))
      (node (ref "C21") (pin "2") (pinfunction "2_2") (pintype "passive"))
      (node (ref "C22") (pin "2") (pinfunction "2_2") (pintype "passive"))
      (node (ref "D17") (pin "2") (pinfunction "K_2") (pintype "passive"))
      (node (ref "D18") (pin "2") (pinfunction "K_2") (pintype "passive"))
      (node (ref "L2") (pin "1") (pinfunction "1_1") (pintype "passive"))
      (node (ref "Q5") (pin "3") (pinfunction "3_3") (pintype "passive"))
      (node (ref "Q6") (pin "3") (pinfunction "3_3") (pintype "passive"))
      (node (ref "Q7") (pin "2") (pinfunction "2_2") (pintype "passive"))
      (node (ref "Q8") (pin "2") (pinfunction "2_2") (pintype "passive"))
      (node (ref "R24") (pin "1") (pinfunction "1_1") (pintype "passive"))
      (node (ref "R25") (pin "1") (pinfunction "1_1") (pintype "passive"))
      (node (ref "R27") (pin "1") (pinfunction "1_1") (pintype "passive"))
      (node (ref "R28") (pin "1") (pinfunction "1_1") (pintype "passive"))
      (node (ref "TP18") (pin "1") (pinfunction "1_1") (pintype "passive"))
      (node (ref "U2") (pin "4") (pinfunction "HS_4") (pintype "passive"))
    )
    (net (code "8") (name "/LSa") (class "Default")
      (node (ref "R11") (pin "1") (pinfunction "1_1") (pintype "passive"))
      (node (ref "U1") (pin "6") (pinfunction "LS_6") (pintype "passive"))
    )
    (net (code "9") (name "/LSb") (class "Default")
      (node (ref "R26") (pin "1") (pinfunction "1_1") (pintype "passive"))
      (node (ref "U2") (pin "6") (pinfunction "LS_6") (pintype "passive"))
    )
    (net (code "10") (name "/PWMb") (class "Default")
      (node (ref "R29") (pin "2") (pinfunction "2_2") (pintype "passive"))
      (node (ref "R45") (pin "1") (pinfunction "1_1") (pintype "passive"))
      (node (ref "R46") (pin "2") (pinfunction "2_2") (pintype "passive"))
      (node (ref "TP17") (pin "1") (pinfunction "1_1") (pintype "passive"))
      (node (ref "U2") (pin "5") (pinfunction "PWM_5") (pintype "passive"))
    )
    (net (code "11") (name "GND") (class "Default")
      (node (ref "C15") (pin "1") (pinfunction "1_1") (pintype "passive"))
      (node (ref "C5") (pin "2") (pinfunction "2_2") (pintype "passive"))
      (node (ref "R14") (pin "1") (pinfunction "1_1") (pintype "passive"))
      (node (ref "R19") (pin "1") (pinfunction "1_1") (pintype "passive"))
      (node (ref "R29") (pin "1") (pinfunction "1_1") (pintype "passive"))
      (node (ref "R30") (pin "1") (pinfunction "1_1") (pintype "passive"))
      (node (ref "U1") (pin "7") (pinfunction "Vss_7") (pintype "passive"))
      (node (ref "U2") (pin "7") (pinfunction "Vss_7") (pintype "passive"))
    )
    (net (code "12") (name "Net-(C1-Pad1)") (class "Default")
      (node (ref "C1") (pin "1") (pinfunction "1_1") (pintype "passive"))
      (node (ref "R8") (pin "2") (pinfunction "2_2") (pintype "passive"))
    )
    (net (code "13") (name "Net-(C2-Pad1)") (class "Default")
      (node (ref "C2") (pin "1") (pinfunction "1_1") (pintype "passive"))
      (node (ref "R7") (pin "2") (pinfunction "2_2") (pintype "passive"))
    )
    (net (code "14") (name "Net-(C11-Pad1)") (class "Default")
      (node (ref "C11") (pin "1") (pinfunction "1_1") (pintype "passive"))
      (node (ref "R15") (pin "2") (pinfunction "2_2") (pintype "passive"))
    )
    (net (code "15") (name "Net-(C12-Pad1)") (class "Default")
      (node (ref "C12") (pin "1") (pinfunction "1_1") (pintype "passive"))
      (node (ref "R17") (pin "2") (pinfunction "2_2") (pintype "passive"))
    )
    (net (code "16") (name "Net-(C13-Pad1)") (class "Default")
      (node (ref "C13") (pin "1") (pinfunction "1_1") (pintype "passive"))
      (node (ref "R27") (pin "2") (pinfunction "2_2") (pintype "passive"))
    )
    (net (code "17") (name "Net-(C14-Pad1)") (class "Default")
      (node (ref "C14") (pin "1") (pinfunction "1_1") (pintype "passive"))
      (node (ref "R28") (pin "2") (pinfunction "2_2") (pintype "passive"))
    )
    (net (code "18") (name "Net-(C21-Pad1)") (class "Default")
      (node (ref "C21") (pin "1") (pinfunction "1_1") (pintype "passive"))
      (node (ref "R37") (pin "2") (pinfunction "2_2") (pintype "passive"))
    )
    (net (code "19") (name "Net-(C22-Pad1)") (class "Default")
      (node (ref "C22") (pin "1") (pinfunction "1_1") (pintype "passive"))
      (node (ref "R38") (pin "2") (pinfunction "2_2") (pintype "passive"))
    )
    (net (code "20") (name "Net-(D1-A)") (class "Default")
      (node (ref "D1") (pin "1") (pinfunction "A_1") (pintype "passive"))
      (node (ref "D4") (pin "2") (pinfunction "K_2") (pintype "passive"))
    )
    (net (code "21") (name "Net-(D1-K)") (class "Default")
      (node (ref "D1") (pin "2") (pinfunction "K_2") (pintype "passive"))
      (node (ref "R1") (pin "2") (pinfunction "2_2") (pintype "passive"))
    )
    (net (code "22") (name "Net-(D2-A)") (class "Default")
      (node (ref "D2") (pin "1") (pinfunction "A_1") (pintype "passive"))
      (node (ref "D3") (pin "2") (pinfunction "K_2") (pintype "passive"))
      (node (ref "Q1") (pin "1") (pinfunction "1_1") (pintype "passive"))
      (node (ref "R4") (pin "2") (pinfunction "2_2") (pintype "passive"))
      (node (ref "R6") (pin "2") (pinfunction "2_2") (pintype "passive"))
    )
    (net (code "23") (name "Net-(D2-K)") (class "Default")
      (node (ref "D2") (pin "2") (pinfunction "K_2") (pintype "passive"))
      (node (ref "R2") (pin "2") (pinfunction "2_2") (pintype "passive"))
    )
    (net (code "24") (name "Net-(D3-A)") (class "Default")
      (node (ref "D3") (pin "1") (pinfunction "A_1") (pintype "passive"))
      (node (ref "D5") (pin "1") (pinfunction "A_1") (pintype "passive"))
    )
    (net (code "25") (name "Net-(D4-A)") (class "Default")
      (node (ref "D4") (pin "1") (pinfunction "A_1") (pintype "passive"))
      (node (ref "D6") (pin "1") (pinfunction "A_1") (pintype "passive"))
    )
    (net (code "26") (name "Net-(D7-A)") (class "Default")
      (node (ref "D7") (pin "1") (pinfunction "A_1") (pintype "passive"))
      (node (ref "D9") (pin "2") (pinfunction "K_2") (pintype "passive"))
    )
    (net (code "27") (name "Net-(D7-K)") (class "Default")
      (node (ref "D7") (pin "2") (pinfunction "K_2") (pintype "passive"))
      (node (ref "R9") (pin "2") (pinfunction "2_2") (pintype "passive"))
    )
    (net (code "28") (name "Net-(D8-K)") (class "Default")
      (node (ref "D8") (pin "2") (pinfunction "K_2") (pintype "passive"))
      (node (ref "R10") (pin "2") (pinfunction "2_2") (pintype "passive"))
    )
    (net (code "29") (name "Net-(D10-A)") (class "Default")
      (node (ref "D10") (pin "1") (pinfunction "A_1") (pintype "passive"))
      (node (ref "D12") (pin "1") (pinfunction "A_1") (pintype "passive"))
    )
    (net (code "30") (name "Net-(D10-K)") (class "Default")
      (node (ref "D10") (pin "2") (pinfunction "K_2") (pintype "passive"))
      (node (ref "D8") (pin "1") (pinfunction "A_1") (pintype "passive"))
      (node (ref "Q4") (pin "1") (pinfunction "1_1") (pintype "passive"))
      (node (ref "R13") (pin "2") (pinfunction "2_2") (pintype "passive"))
      (node (ref "R18") (pin "2") (pinfunction "2_2") (pintype "passive"))
    )
    (net (code "31") (name "Net-(D11-A)") (class "Default")
      (node (ref "D11") (pin "1") (pinfunction "A_1") (pintype "passive"))
      (node (ref "D9") (pin "1") (pinfunction "A_1") (pintype "passive"))
    )
    (net (code "32") (name "Net-(D13-A)") (class "Default")
      (node (ref "D13") (pin "1") (pinfunction "A_1") (pintype "passive"))
      (node (ref "D15") (pin "2") (pinfunction "K_2") (pintype "passive"))
      (node (ref "Q5") (pin "1") (pinfunction "1_1") (pintype "passive"))
      (node (ref "R22") (pin "2") (pinfunction "2_2") (pintype "passive"))
      (node (ref "R24") (pin "2") (pinfunction "2_2") (pintype "passive"))
    )
    (net (code "33") (name "Net-(D13-K)") (class "Default")
      (node (ref "D13") (pin "2") (pinfunction "K_2") (pintype "passive"))
      (node (ref "R20") (pin "2") (pinfunction "2_2") (pintype "passive"))
    )
    (net (code "34") (name "Net-(D14-A)") (class "Default")
      (node (ref "D14") (pin "1") (pinfunction "A_1") (pintype "passive"))
      (node (ref "D16") (pin "2") (pinfunction "K_2") (pintype "passive"))
    )
    (net (code "35") (name "Net-(D14-K)") (class "Default")
      (node (ref "D14") (pin "2") (pinfunction "K_2") (pintype "passive"))
      (node (ref "R21") (pin "2") (pinfunction "2_2") (pintype "passive"))
    )
    (net (code "36") (name "Net-(D15-A)") (class "Default")
      (node (ref "D15") (pin "1") (pinfunction "A_1") (pintype "passive"))
      (node (ref "D17") (pin "1") (pinfunction "A_1") (pintype "passive"))
    )
    (net (code "37") (name "Net-(D16-A)") (class "Default")
      (node (ref "D16") (pin "1") (pinfunction "A_1") (pintype "passive"))
      (node (ref "D18") (pin "1") (pinfunction "A_1") (pintype "passive"))
    )
    (net (code "38") (name "Net-(D19-A)") (class "Default")
      (node (ref "D19") (pin "1") (pinfunction "A_1") (pintype "passive"))
      (node (ref "D21") (pin "2") (pinfunction "K_2") (pintype "passive"))
    )
    (net (code "39") (name "Net-(D19-K)") (class "Default")
      (node (ref "D19") (pin "2") (pinfunction "K_2") (pintype "passive"))
      (node (ref "R31") (pin "2") (pinfunction "2_2") (pintype "passive"))
    )
    (net (code "40") (name "Net-(D20-A)") (class "Default")
      (node (ref "D20") (pin "1") (pinfunction "A_1") (pintype "passive"))
      (node (ref "D22") (pin "2") (pinfunction "K_2") (pintype "passive"))
    )
    (net (code "41") (name "Net-(D20-K)") (class "Default")
      (node (ref "D20") (pin "2") (pinfunction "K_2") (pintype "passive"))
      (node (ref "R32") (pin "2") (pinfunction "2_2") (pintype "passive"))
    )
    (net (code "42") (name "Net-(D21-A)") (class "Default")
      (node (ref "D21") (pin "1") (pinfunction "A_1") (pintype "passive"))
      (node (ref "D23") (pin "1") (pinfunction "A_1") (pintype "passive"))
    )
    (net (code "43") (name "Net-(D22-A)") (class "Default")
      (node (ref "D22") (pin "1") (pinfunction "A_1") (pintype "passive"))
      (node (ref "D24") (pin "1") (pinfunction "A_1") (pintype "passive"))
    )
    (net (code "44") (name "Net-(Q2-Pad1)") (class "Default")
      (node (ref "Q2") (pin "1") (pinfunction "1_1") (pintype "passive"))
      (node (ref "R3") (pin "2") (pinfunction "2_2") (pintype "passive"))
      (node (ref "R5") (pin "2") (pinfunction "2_2") (pintype "passive"))
    )
    (net (code "45") (name "Net-(Q3-Pad1)") (class "Default")
      (node (ref "Q3") (pin "1") (pinfunction "1_1") (pintype "passive"))
      (node (ref "R12") (pin "2") (pinfunction "2_2") (pintype "passive"))
      (node (ref "R16") (pin "2") (pinfunction "2_2") (pintype "passive"))
    )
    (net (code "46") (name "Net-(Q6-Pad1)") (class "Default")
      (node (ref "Q6") (pin "1") (pinfunction "1_1") (pintype "passive"))
      (node (ref "R23") (pin "2") (pinfunction "2_2") (pintype "passive"))
      (node (ref "R25") (pin "2") (pinfunction "2_2") (pintype "passive"))
    )
    (net (code "47") (name "Net-(Q7-Pad1)") (class "Default")
      (node (ref "Q7") (pin "1") (pinfunction "1_1") (pintype "passive"))
      (node (ref "R33") (pin "2") (pinfunction "2_2") (pintype "passive"))
      (node (ref "R35") (pin "2") (pinfunction "2_2") (pintype "passive"))
    )
    (net (code "48") (name "Net-(Q8-Pad1)") (class "Default")
      (node (ref "Q8") (pin "1") (pinfunction "1_1") (pintype "passive"))
      (node (ref "R34") (pin "2") (pinfunction "2_2") (pintype "passive"))
      (node (ref "R36") (pin "2") (pinfunction "2_2") (pintype "passive"))
    )
    (net (code "49") (name "Net-(R39-PadI2)") (class "Default")
      (node (ref "R39") (pin "I2") (pinfunction "I2_I2") (pintype "passive"))
      (node (ref "T1") (pin "1") (pinfunction "1_1") (pintype "passive"))
    )
    (net (code "50") (name "Net-(U1-HB)") (class "Default")
      (node (ref "C8") (pin "2") (pinfunction "2_2") (pintype "passive"))
      (node (ref "U1") (pin "2") (pinfunction "HB_2") (pintype "passive"))
    )
    (net (code "51") (name "Net-(U2-HB)") (class "Default")
      (node (ref "C16") (pin "2") (pinfunction "2_2") (pintype "passive"))
      (node (ref "U2") (pin "2") (pinfunction "HB_2") (pintype "passive"))
    )
    (net (code "52") (name "PWM_a") (class "Default")
      (node (ref "R14") (pin "2") (pinfunction "2_2") (pintype "passive"))
      (node (ref "R45") (pin "2") (pinfunction "2_2") (pintype "passive"))
      (node (ref "TP13") (pin "1") (pinfunction "1_1") (pintype "passive"))
      (node (ref "U1") (pin "5") (pinfunction "PWM_5") (pintype "passive"))
    )
    (net (code "53") (name "PWM_b") (class "Default")
      (node (ref "R46") (pin "1") (pinfunction "1_1") (pintype "passive"))
    )
    (net (code "54") (name "P_GND") (class "Default")
      (node (ref "C10") (pin "1") (pinfunction "1_1") (pintype "passive"))
      (node (ref "C17") (pin "2") (pinfunction "2_2") (pintype "passive"))
      (node (ref "C18") (pin "2") (pinfunction "2_2") (pintype "passive"))
      (node (ref "C19") (pin "1") (pinfunction "1_1") (pintype "passive"))
      (node (ref "C20") (pin "1") (pinfunction "1_1") (pintype "passive"))
      (node (ref "C3") (pin "2") (pinfunction "2_2") (pintype "passive"))
      (node (ref "C4") (pin "2") (pinfunction "2_2") (pintype "passive"))
      (node (ref "C6") (pin "2") (pinfunction "2_2") (pintype "passive"))
      (node (ref "C7") (pin "2") (pinfunction "2_2") (pintype "passive"))
      (node (ref "C9") (pin "1") (pinfunction "1_1") (pintype "passive"))
      (node (ref "D11") (pin "2") (pinfunction "K_2") (pintype "passive"))
      (node (ref "D12") (pin "2") (pinfunction "K_2") (pintype "passive"))
      (node (ref "D23") (pin "2") (pinfunction "K_2") (pintype "passive"))
      (node (ref "D24") (pin "2") (pinfunction "K_2") (pintype "passive"))
      (node (ref "J7") (pin "1") (pinfunction "1_1") (pintype "passive"))
      (node (ref "Q3") (pin "3") (pinfunction "3_3") (pintype "passive"))
      (node (ref "Q4") (pin "3") (pinfunction "3_3") (pintype "passive"))
      (node (ref "Q7") (pin "3") (pinfunction "3_3") (pintype "passive"))
      (node (ref "Q8") (pin "3") (pinfunction "3_3") (pintype "passive"))
      (node (ref "R15") (pin "1") (pinfunction "1_1") (pintype "passive"))
      (node (ref "R16") (pin "1") (pinfunction "1_1") (pintype "passive"))
      (node (ref "R17") (pin "1") (pinfunction "1_1") (pintype "passive"))
      (node (ref "R18") (pin "1") (pinfunction "1_1") (pintype "passive"))
      (node (ref "R19") (pin "2") (pinfunction "2_2") (pintype "passive"))
      (node (ref "R30") (pin "2") (pinfunction "2_2") (pintype "passive"))
      (node (ref "R35") (pin "1") (pinfunction "1_1") (pintype "passive"))
      (node (ref "R36") (pin "1") (pinfunction "1_1") (pintype "passive"))
      (node (ref "R37") (pin "1") (pinfunction "1_1") (pintype "passive"))
      (node (ref "R38") (pin "1") (pinfunction "1_1") (pintype "passive"))
      (node (ref "T2") (pin "1") (pinfunction "1_1") (pintype "passive"))
    )
    (net (code "55") (name "Shunt+") (class "Default")
      (node (ref "R39") (pin "U1") (pinfunction "U1_U1") (pintype "passive"))
    )
    (net (code "56") (name "Shunt-") (class "Default")
      (node (ref "R39") (pin "U2") (pinfunction "U2_U2") (pintype "passive"))
    )
    (net (code "57") (name "Vbat") (class "Default")
      (node (ref "C1") (pin "2") (pinfunction "2_2") (pintype "passive"))
      (node (ref "C13") (pin "2") (pinfunction "2_2") (pintype "passive"))
      (node (ref "C14") (pin "2") (pinfunction "2_2") (pintype "passive"))
      (node (ref "C2") (pin "2") (pinfunction "2_2") (pintype "passive"))
      (node (ref "C3") (pin "1") (pinfunction "1_1") (pintype "passive"))
      (node (ref "C4") (pin "1") (pinfunction "1_1") (pintype "passive"))
      (node (ref "J6") (pin "1") (pinfunction "1_1") (pintype "passive"))
      (node (ref "Q1") (pin "2") (pinfunction "2_2") (pintype "passive"))
      (node (ref "Q2") (pin "2") (pinfunction "2_2") (pintype "passive"))
      (node (ref "Q5") (pin "2") (pinfunction "2_2") (pintype "passive"))
      (node (ref "Q6") (pin "2") (pinfunction "2_2") (pintype "passive"))
    )
    (net (code "58") (name "Vout+") (class "Default")
      (node (ref "C10") (pin "2") (pinfunction "2_2") (pintype "passive"))
      (node (ref "C17") (pin "1") (pinfunction "1_1") (pintype "passive"))
      (node (ref "C18") (pin "1") (pinfunction "1_1") (pintype "passive"))
      (node (ref "C19") (pin "2") (pinfunction "2_2") (pintype "passive"))
      (node (ref "C20") (pin "2") (pinfunction "2_2") (pintype "passive"))
      (node (ref "C6") (pin "1") (pinfunction "1_1") (pintype "passive"))
      (node (ref "C7") (pin "1") (pinfunction "1_1") (pintype "passive"))
      (node (ref "C9") (pin "2") (pinfunction "2_2") (pintype "passive"))
      (node (ref "L1") (pin "2") (pinfunction "2_2") (pintype "passive"))
      (node (ref "L2") (pin "2") (pinfunction "2_2") (pintype "passive"))
      (node (ref "R39") (pin "I1") (pinfunction "I1_I1") (pintype "passive"))
    )
    (net (code "59") (name "unconnected-(L1-Pad3)") (class "Default")
      (node (ref "L1") (pin "3") (pinfunction "3_3") (pintype "passive"))
    )
    (net (code "60") (name "unconnected-(L2-Pad3)") (class "Default")
      (node (ref "L2") (pin "3") (pinfunction "3_3") (pintype "passive"))
    )
  )
)
